# Power.net
KiCad netlist of a schematic drawn in Altium Designer
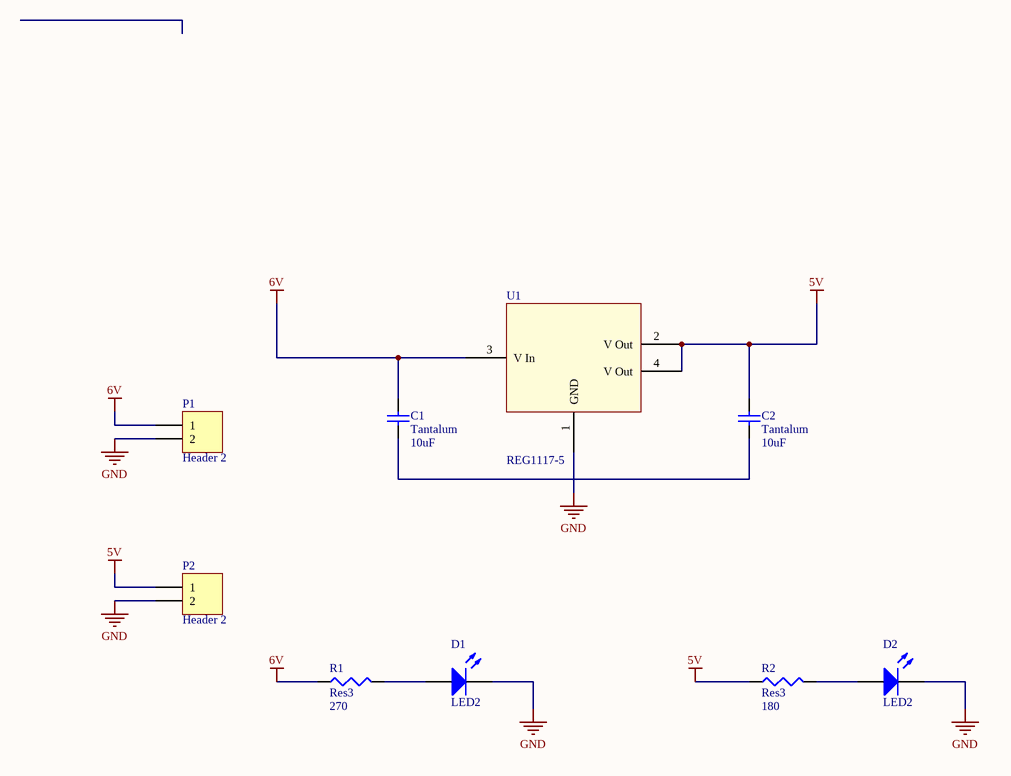
[diagram p0: Power.SchDoc]

(export (version "E")
  (design (tool "Eeschema 10.0.6"))
  (components
    (comp (ref "C1")
      (value "Tantalum")
      (footprint "C1206")
      (description "Capacitor (Semiconductor SIM Model)")
      (fields (field (name "ALTIUM_VALUE") "10uF") (field (name "PUBLISHER") "Altium Limited"))
      (libsource (lib "Miscellaneous Devices") (part "Cap Semi"))
    )
    (comp (ref "C2")
      (value "Tantalum")
      (footprint "C1206")
      (description "Capacitor (Semiconductor SIM Model)")
      (fields (field (name "ALTIUM_VALUE") "10uF") (field (name "PUBLISHER") "Altium Limited"))
      (libsource (lib "") (part "Cap Semi_1"))
    )
    (comp (ref "D1")
      (value "LED2")
      (footprint "3.2X1.6X1.1")
      (description "Typical RED, GREEN, YELLOW, AMBER GaAs LED")
      (fields (field (name "PUBLISHER") "Altium Limited"))
      (libsource (lib "Miscellaneous Devices") (part "LED2"))
    )
    (comp (ref "D2")
      (value "LED2")
      (footprint "3.2X1.6X1.1")
      (description "Typical RED, GREEN, YELLOW, AMBER GaAs LED")
      (fields (field (name "PUBLISHER") "Altium Limited"))
      (libsource (lib "Miscellaneous Devices") (part "LED2"))
    )
    (comp (ref "P1")
      (value "Header 2")
      (footprint "HDR1X2")
      (description "Header, 2-Pin")
      (fields (field (name "PUBLISHER") "Altium Limited"))
      (libsource (lib "Miscellaneous Connectors") (part "Header 2"))
    )
    (comp (ref "P2")
      (value "Header 2")
      (footprint "HDR1X2")
      (description "Header, 2-Pin")
      (fields (field (name "PUBLISHER") "Altium Limited"))
      (libsource (lib "Miscellaneous Connectors") (part "Header 2"))
    )
    (comp (ref "R1")
      (value "Res3")
      (footprint "J1-0603")
      (description "Resistor")
      (fields (field (name "ALTIUM_VALUE") "270") (field (name "PUBLISHER") "Altium Limited"))
      (libsource (lib "Miscellaneous Devices") (part "Res3"))
    )
    (comp (ref "R2")
      (value "Res3")
      (footprint "J1-0603")
      (description "Resistor")
      (fields (field (name "ALTIUM_VALUE") "180") (field (name "PUBLISHER") "Altium Limited"))
      (libsource (lib "Miscellaneous Devices") (part "Res3"))
    )
    (comp (ref "U1")
      (value "REG1117-5")
      (footprint "SOT230P710X180-4N")
      (description "REG1117-5, Voltage Regulator, 5V Out, 800mA")
      (libsource (lib "REG1117-5") (part "REG1117-5"))
    )
  )
  (nets
    (net (code "1") (name "5V") (class "Default")
      (node (ref "C2") (pin "2") (pinfunction "2_2") (pintype "passive"))
      (node (ref "P2") (pin "1") (pinfunction "1_1") (pintype "passive"))
      (node (ref "R2") (pin "1") (pinfunction "1_1") (pintype "passive"))
      (node (ref "U1") (pin "2") (pinfunction "V_Out_2") (pintype "passive"))
      (node (ref "U1") (pin "4") (pinfunction "V_Out_4") (pintype "passive"))
    )
    (net (code "2") (name "6V") (class "Default")
      (node (ref "C1") (pin "1") (pinfunction "1_1") (pintype "passive"))
      (node (ref "P1") (pin "1") (pinfunction "1_1") (pintype "passive"))
      (node (ref "R1") (pin "1") (pinfunction "1_1") (pintype "passive"))
      (node (ref "U1") (pin "3") (pinfunction "V_In_3") (pintype "passive"))
    )
    (net (code "3") (name "GND") (class "Default")
      (node (ref "D1") (pin "2") (pinfunction "K_2") (pintype "passive"))
      (node (ref "D2") (pin "2") (pinfunction "K_2") (pintype "passive"))
      (node (ref "P1") (pin "2") (pinfunction "2_2") (pintype "passive"))
      (node (ref "P2") (pin "2") (pinfunction "2_2") (pintype "passive"))
      (node (ref "U1") (pin "1") (pinfunction "GND_1") (pintype "passive"))
    )
    (net (code "4") (name "Net-(C1-Pad2)") (class "Default")
      (node (ref "C1") (pin "2") (pinfunction "2_2") (pintype "passive"))
      (node (ref "C2") (pin "1") (pinfunction "1_1") (pintype "passive"))
    )
    (net (code "5") (name "Net-(D1-A)") (class "Default")
      (node (ref "D1") (pin "1") (pinfunction "A_1") (pintype "passive"))
      (node (ref "R1") (pin "2") (pinfunction "2_2") (pintype "passive"))
    )
    (net (code "6") (name "Net-(D2-A)") (class "Default")
      (node (ref "D2") (pin "1") (pinfunction "A_1") (pintype "passive"))
      (node (ref "R2") (pin "2") (pinfunction "2_2") (pintype "passive"))
    )
  )
)
